# ESC_2S.net
KiCad netlist of a schematic drawn in Altium Designer
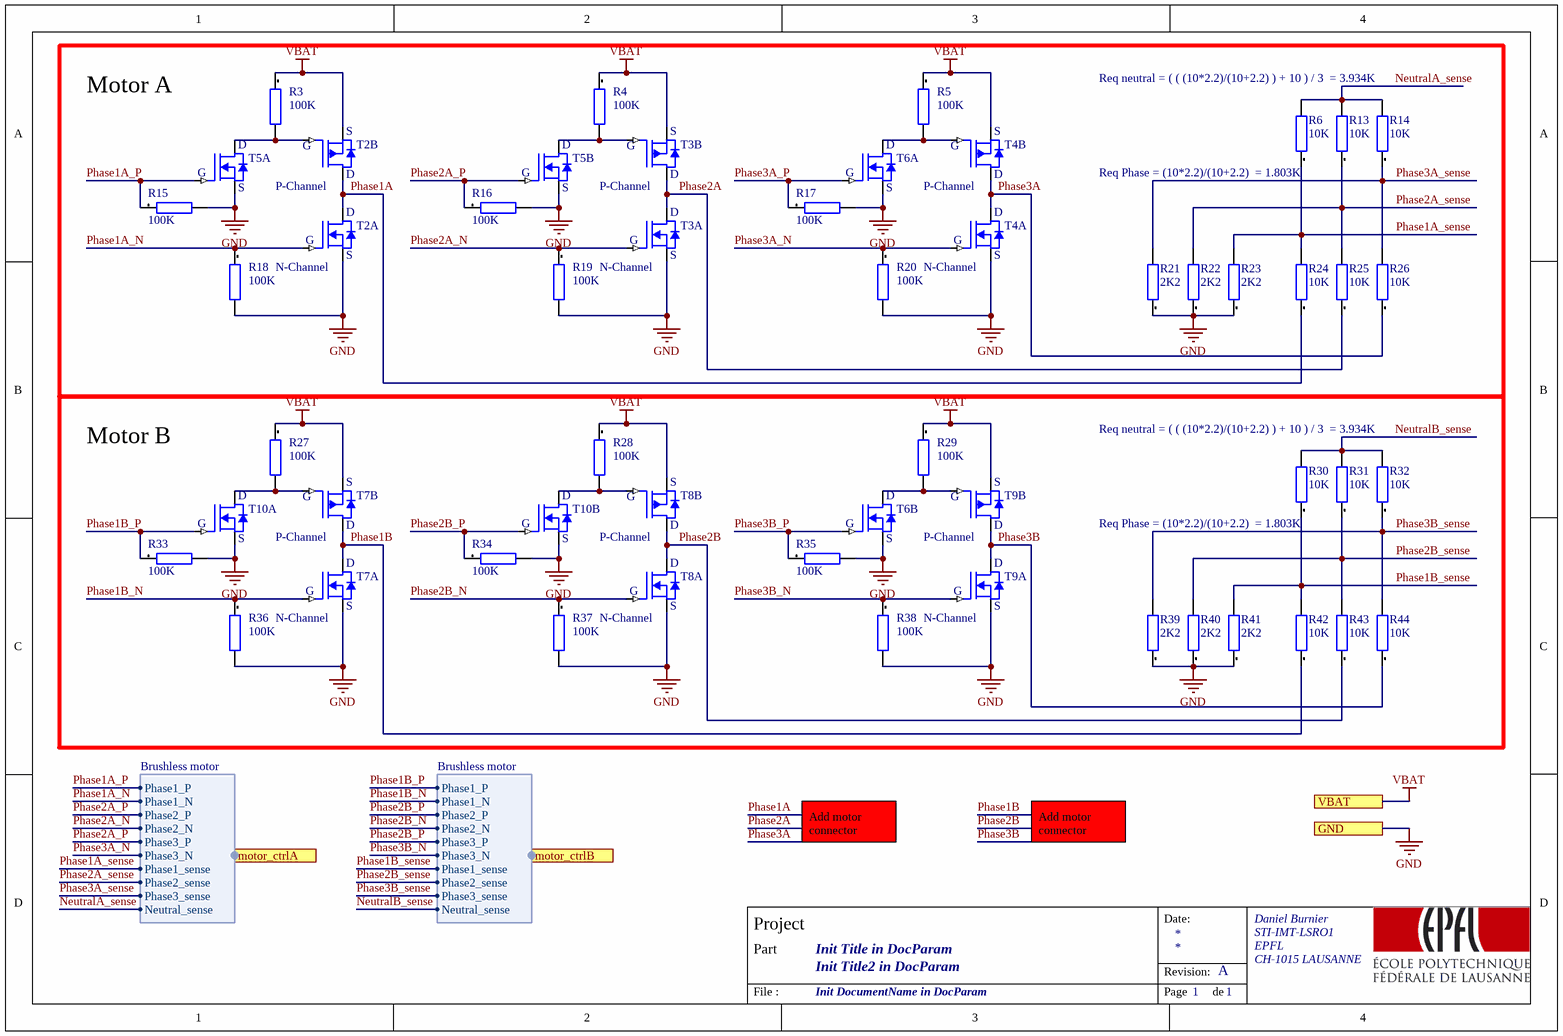
[diagram p0: ESC_2S.SchDoc]

(export (version "E")
  (design (tool "Eeschema 10.0.6"))
  (components
    (comp (ref "R3")
      (value "100K")
      (footprint "RESC0201(0603)_L")
      (description "Resistor ToDo 0201")
      (libsource (lib "LSRO1Altium") (part "RES"))
    )
    (comp (ref "R4")
      (value "100K")
      (footprint "RESC0201(0603)_L")
      (description "Resistor ToDo 0201")
      (libsource (lib "LSRO1Altium") (part "RES"))
    )
    (comp (ref "R5")
      (value "100K")
      (footprint "RESC0201(0603)_L")
      (description "Resistor ToDo 0201")
      (libsource (lib "LSRO1Altium") (part "RES"))
    )
    (comp (ref "R6")
      (value "10K")
      (footprint "RESC0201(0603)_L")
      (description "Resistor ToDo 0201")
      (libsource (lib "LSRO1Altium") (part "RES"))
    )
    (comp (ref "R13")
      (value "10K")
      (footprint "RESC0201(0603)_L")
      (description "Resistor ToDo 0201")
      (libsource (lib "LSRO1Altium") (part "RES"))
    )
    (comp (ref "R14")
      (value "10K")
      (footprint "RESC0201(0603)_L")
      (description "Resistor ToDo 0201")
      (libsource (lib "LSRO1Altium") (part "RES"))
    )
    (comp (ref "R15")
      (value "100K")
      (footprint "RESC0201(0603)_L")
      (description "Resistor ToDo 0201")
      (libsource (lib "LSRO1Altium") (part "RES"))
    )
    (comp (ref "R16")
      (value "100K")
      (footprint "RESC0201(0603)_L")
      (description "Resistor ToDo 0201")
      (libsource (lib "LSRO1Altium") (part "RES"))
    )
    (comp (ref "R17")
      (value "100K")
      (footprint "RESC0201(0603)_L")
      (description "Resistor ToDo 0201")
      (libsource (lib "LSRO1Altium") (part "RES"))
    )
    (comp (ref "R18")
      (value "100K")
      (footprint "RESC0201(0603)_L")
      (description "Resistor ToDo 0201")
      (libsource (lib "LSRO1Altium") (part "RES"))
    )
    (comp (ref "R19")
      (value "100K")
      (footprint "RESC0201(0603)_L")
      (description "Resistor ToDo 0201")
      (libsource (lib "LSRO1Altium") (part "RES"))
    )
    (comp (ref "R20")
      (value "100K")
      (footprint "RESC0201(0603)_L")
      (description "Resistor ToDo 0201")
      (libsource (lib "LSRO1Altium") (part "RES"))
    )
    (comp (ref "R21")
      (value "2K2")
      (footprint "RESC0201(0603)_L")
      (description "Resistor ToDo 0201")
      (libsource (lib "LSRO1Altium") (part "RES"))
    )
    (comp (ref "R22")
      (value "2K2")
      (footprint "RESC0201(0603)_L")
      (description "Resistor ToDo 0201")
      (libsource (lib "LSRO1Altium") (part "RES"))
    )
    (comp (ref "R23")
      (value "2K2")
      (footprint "RESC0201(0603)_L")
      (description "Resistor ToDo 0201")
      (libsource (lib "LSRO1Altium") (part "RES"))
    )
    (comp (ref "R24")
      (value "10K")
      (footprint "RESC0201(0603)_L")
      (description "Resistor ToDo 0201")
      (libsource (lib "LSRO1Altium") (part "RES"))
    )
    (comp (ref "R25")
      (value "10K")
      (footprint "RESC0201(0603)_L")
      (description "Resistor ToDo 0201")
      (libsource (lib "LSRO1Altium") (part "RES"))
    )
    (comp (ref "R26")
      (value "10K")
      (footprint "RESC0201(0603)_L")
      (description "Resistor ToDo 0201")
      (libsource (lib "LSRO1Altium") (part "RES"))
    )
    (comp (ref "R27")
      (value "100K")
      (footprint "RESC0201(0603)_L")
      (description "Resistor ToDo 0201")
      (libsource (lib "LSRO1Altium") (part "RES"))
    )
    (comp (ref "R28")
      (value "100K")
      (footprint "RESC0201(0603)_L")
      (description "Resistor ToDo 0201")
      (libsource (lib "LSRO1Altium") (part "RES"))
    )
    (comp (ref "R29")
      (value "100K")
      (footprint "RESC0201(0603)_L")
      (description "Resistor ToDo 0201")
      (libsource (lib "LSRO1Altium") (part "RES"))
    )
    (comp (ref "R30")
      (value "10K")
      (footprint "RESC0201(0603)_L")
      (description "Resistor ToDo 0201")
      (libsource (lib "LSRO1Altium") (part "RES"))
    )
    (comp (ref "R31")
      (value "10K")
      (footprint "RESC0201(0603)_L")
      (description "Resistor ToDo 0201")
      (libsource (lib "LSRO1Altium") (part "RES"))
    )
    (comp (ref "R32")
      (value "10K")
      (footprint "RESC0201(0603)_L")
      (description "Resistor ToDo 0201")
      (libsource (lib "LSRO1Altium") (part "RES"))
    )
    (comp (ref "R33")
      (value "100K")
      (footprint "RESC0201(0603)_L")
      (description "Resistor ToDo 0201")
      (libsource (lib "LSRO1Altium") (part "RES"))
    )
    (comp (ref "R34")
      (value "100K")
      (footprint "RESC0201(0603)_L")
      (description "Resistor ToDo 0201")
      (libsource (lib "LSRO1Altium") (part "RES"))
    )
    (comp (ref "R35")
      (value "100K")
      (footprint "RESC0201(0603)_L")
      (description "Resistor ToDo 0201")
      (libsource (lib "LSRO1Altium") (part "RES"))
    )
    (comp (ref "R36")
      (value "100K")
      (footprint "RESC0201(0603)_L")
      (description "Resistor ToDo 0201")
      (libsource (lib "LSRO1Altium") (part "RES"))
    )
    (comp (ref "R37")
      (value "100K")
      (footprint "RESC0201(0603)_L")
      (description "Resistor ToDo 0201")
      (libsource (lib "LSRO1Altium") (part "RES"))
    )
    (comp (ref "R38")
      (value "100K")
      (footprint "RESC0201(0603)_L")
      (description "Resistor ToDo 0201")
      (libsource (lib "LSRO1Altium") (part "RES"))
    )
    (comp (ref "R39")
      (value "2K2")
      (footprint "RESC0201(0603)_L")
      (description "Resistor ToDo 0201")
      (libsource (lib "LSRO1Altium") (part "RES"))
    )
    (comp (ref "R40")
      (value "2K2")
      (footprint "RESC0201(0603)_L")
      (description "Resistor ToDo 0201")
      (libsource (lib "LSRO1Altium") (part "RES"))
    )
    (comp (ref "R41")
      (value "2K2")
      (footprint "RESC0201(0603)_L")
      (description "Resistor ToDo 0201")
      (libsource (lib "LSRO1Altium") (part "RES"))
    )
    (comp (ref "R42")
      (value "10K")
      (footprint "RESC0201(0603)_L")
      (description "Resistor ToDo 0201")
      (libsource (lib "LSRO1Altium") (part "RES"))
    )
    (comp (ref "R43")
      (value "10K")
      (footprint "RESC0201(0603)_L")
      (description "Resistor ToDo 0201")
      (libsource (lib "LSRO1Altium") (part "RES"))
    )
    (comp (ref "R44")
      (value "10K")
      (footprint "RESC0201(0603)_L")
      (description "Resistor ToDo 0201")
      (libsource (lib "LSRO1Altium") (part "RES"))
    )
    (comp (ref "T2")
      (value "ECH8668-TL-H")
      (footprint "8-SMD Flat lead")
      (description "MOSFET N/P-CH 20V 7.5A/5A ECH8")
      (fields (field (name "MANUFACTURER") "ON Semiconductor"))
      (libsource (lib "Schlib") (part "ECH8668-TL-H"))
    )
    (comp (ref "T3")
      (value "ECH8668-TL-H")
      (footprint "8-SMD Flat lead")
      (description "MOSFET N/P-CH 20V 7.5A/5A ECH8")
      (fields (field (name "MANUFACTURER") "ON Semiconductor"))
      (libsource (lib "Schlib") (part "ECH8668-TL-H"))
    )
    (comp (ref "T4")
      (value "ECH8668-TL-H")
      (footprint "8-SMD Flat lead")
      (description "MOSFET N/P-CH 20V 7.5A/5A ECH8")
      (fields (field (name "MANUFACTURER") "ON Semiconductor"))
      (libsource (lib "Schlib") (part "ECH8668-TL-H"))
    )
    (comp (ref "T5")
      (value "PMDXB550UNEZ")
      (footprint "DFN1010B-6")
      (description "DUAL N-CHANNEL 30V")
      (fields (field (name "MANUFACTURER") "NXP Semiconductors"))
      (libsource (lib "Schlib") (part "PMDXB550UNEZ"))
    )
    (comp (ref "T6")
      (value "PMDXB550UNEZ")
      (footprint "DFN1010B-6")
      (description "DUAL N-CHANNEL 30V")
      (fields (field (name "MANUFACTURER") "NXP Semiconductors"))
      (libsource (lib "Schlib") (part "PMDXB550UNEZ"))
    )
    (comp (ref "T7")
      (value "ECH8668-TL-H")
      (footprint "8-SMD Flat lead")
      (description "MOSFET N/P-CH 20V 7.5A/5A ECH8")
      (fields (field (name "MANUFACTURER") "ON Semiconductor"))
      (libsource (lib "Schlib") (part "ECH8668-TL-H"))
    )
    (comp (ref "T8")
      (value "ECH8668-TL-H")
      (footprint "8-SMD Flat lead")
      (description "MOSFET N/P-CH 20V 7.5A/5A ECH8")
      (fields (field (name "MANUFACTURER") "ON Semiconductor"))
      (libsource (lib "Schlib") (part "ECH8668-TL-H"))
    )
    (comp (ref "T9")
      (value "ECH8668-TL-H")
      (footprint "8-SMD Flat lead")
      (description "MOSFET N/P-CH 20V 7.5A/5A ECH8")
      (fields (field (name "MANUFACTURER") "ON Semiconductor"))
      (libsource (lib "Schlib") (part "ECH8668-TL-H"))
    )
    (comp (ref "T10")
      (value "PMDXB550UNEZ")
      (footprint "DFN1010B-6")
      (description "DUAL N-CHANNEL 30V")
      (fields (field (name "MANUFACTURER") "NXP Semiconductors"))
      (libsource (lib "Schlib") (part "PMDXB550UNEZ"))
    )
  )
  (nets
    (net (code "3") (name "/NeutralA_sense") (class "Default")
      (node (ref "R13") (pin "2") (pinfunction "2_2") (pintype "passive"))
      (node (ref "R14") (pin "2") (pinfunction "2_2") (pintype "passive"))
      (node (ref "R6") (pin "2") (pinfunction "2_2") (pintype "passive"))
    )
    (net (code "4") (name "/NeutralB_sense") (class "Default")
      (node (ref "R30") (pin "2") (pinfunction "2_2") (pintype "passive"))
      (node (ref "R31") (pin "2") (pinfunction "2_2") (pintype "passive"))
      (node (ref "R32") (pin "2") (pinfunction "2_2") (pintype "passive"))
    )
    (net (code "5") (name "/Phase1A") (class "Default")
      (node (ref "R24") (pin "1") (pinfunction "1_1") (pintype "passive"))
      (node (ref "T2") (pin "5") (pinfunction "D_5") (pintype "passive"))
      (node (ref "T2") (pin "6") (pinfunction "D_6") (pintype "passive"))
    )
    (net (code "6") (name "/Phase1A_N") (class "Default")
      (node (ref "R18") (pin "1") (pinfunction "1_1") (pintype "passive"))
      (node (ref "T2") (pin "2") (pinfunction "G_2") (pintype "input"))
    )
    (net (code "7") (name "/Phase1A_P") (class "Default")
      (node (ref "R15") (pin "1") (pinfunction "1_1") (pintype "passive"))
      (node (ref "T5") (pin "2") (pinfunction "G_2") (pintype "input"))
    )
    (net (code "8") (name "/Phase1A_sense") (class "Default")
      (node (ref "R23") (pin "2") (pinfunction "2_2") (pintype "passive"))
      (node (ref "R24") (pin "2") (pinfunction "2_2") (pintype "passive"))
      (node (ref "R6") (pin "1") (pinfunction "1_1") (pintype "passive"))
    )
    (net (code "9") (name "/Phase1B") (class "Default")
      (node (ref "R42") (pin "1") (pinfunction "1_1") (pintype "passive"))
      (node (ref "T7") (pin "5") (pinfunction "D_5") (pintype "passive"))
      (node (ref "T7") (pin "6") (pinfunction "D_6") (pintype "passive"))
    )
    (net (code "10") (name "/Phase1B_N") (class "Default")
      (node (ref "R36") (pin "1") (pinfunction "1_1") (pintype "passive"))
      (node (ref "T7") (pin "2") (pinfunction "G_2") (pintype "input"))
    )
    (net (code "11") (name "/Phase1B_P") (class "Default")
      (node (ref "R33") (pin "1") (pinfunction "1_1") (pintype "passive"))
      (node (ref "T10") (pin "2") (pinfunction "G_2") (pintype "input"))
    )
    (net (code "12") (name "/Phase1B_sense") (class "Default")
      (node (ref "R30") (pin "1") (pinfunction "1_1") (pintype "passive"))
      (node (ref "R41") (pin "2") (pinfunction "2_2") (pintype "passive"))
      (node (ref "R42") (pin "2") (pinfunction "2_2") (pintype "passive"))
    )
    (net (code "13") (name "/Phase2A") (class "Default")
      (node (ref "R25") (pin "1") (pinfunction "1_1") (pintype "passive"))
      (node (ref "T3") (pin "5") (pinfunction "D_5") (pintype "passive"))
      (node (ref "T3") (pin "6") (pinfunction "D_6") (pintype "passive"))
    )
    (net (code "14") (name "/Phase2A_N") (class "Default")
      (node (ref "R19") (pin "1") (pinfunction "1_1") (pintype "passive"))
      (node (ref "T3") (pin "2") (pinfunction "G_2") (pintype "input"))
    )
    (net (code "15") (name "/Phase2A_P") (class "Default")
      (node (ref "R16") (pin "1") (pinfunction "1_1") (pintype "passive"))
      (node (ref "T5") (pin "5") (pinfunction "G_5") (pintype "input"))
    )
    (net (code "16") (name "/Phase2A_sense") (class "Default")
      (node (ref "R13") (pin "1") (pinfunction "1_1") (pintype "passive"))
      (node (ref "R22") (pin "2") (pinfunction "2_2") (pintype "passive"))
      (node (ref "R25") (pin "2") (pinfunction "2_2") (pintype "passive"))
    )
    (net (code "17") (name "/Phase2B") (class "Default")
      (node (ref "R43") (pin "1") (pinfunction "1_1") (pintype "passive"))
      (node (ref "T8") (pin "5") (pinfunction "D_5") (pintype "passive"))
      (node (ref "T8") (pin "6") (pinfunction "D_6") (pintype "passive"))
    )
    (net (code "18") (name "/Phase2B_N") (class "Default")
      (node (ref "R37") (pin "1") (pinfunction "1_1") (pintype "passive"))
      (node (ref "T8") (pin "2") (pinfunction "G_2") (pintype "input"))
    )
    (net (code "19") (name "/Phase2B_P") (class "Default")
      (node (ref "R34") (pin "1") (pinfunction "1_1") (pintype "passive"))
      (node (ref "T10") (pin "5") (pinfunction "G_5") (pintype "input"))
    )
    (net (code "20") (name "/Phase2B_sense") (class "Default")
      (node (ref "R31") (pin "1") (pinfunction "1_1") (pintype "passive"))
      (node (ref "R40") (pin "2") (pinfunction "2_2") (pintype "passive"))
      (node (ref "R43") (pin "2") (pinfunction "2_2") (pintype "passive"))
    )
    (net (code "21") (name "/Phase3A") (class "Default")
      (node (ref "R26") (pin "1") (pinfunction "1_1") (pintype "passive"))
      (node (ref "T4") (pin "5") (pinfunction "D_5") (pintype "passive"))
      (node (ref "T4") (pin "6") (pinfunction "D_6") (pintype "passive"))
    )
    (net (code "22") (name "/Phase3A_N") (class "Default")
      (node (ref "R20") (pin "1") (pinfunction "1_1") (pintype "passive"))
      (node (ref "T4") (pin "2") (pinfunction "G_2") (pintype "input"))
    )
    (net (code "23") (name "/Phase3A_P") (class "Default")
      (node (ref "R17") (pin "1") (pinfunction "1_1") (pintype "passive"))
      (node (ref "T6") (pin "2") (pinfunction "G_2") (pintype "input"))
    )
    (net (code "24") (name "/Phase3A_sense") (class "Default")
      (node (ref "R14") (pin "1") (pinfunction "1_1") (pintype "passive"))
      (node (ref "R21") (pin "2") (pinfunction "2_2") (pintype "passive"))
      (node (ref "R26") (pin "2") (pinfunction "2_2") (pintype "passive"))
    )
    (net (code "25") (name "/Phase3B") (class "Default")
      (node (ref "R44") (pin "1") (pinfunction "1_1") (pintype "passive"))
      (node (ref "T9") (pin "5") (pinfunction "D_5") (pintype "passive"))
      (node (ref "T9") (pin "6") (pinfunction "D_6") (pintype "passive"))
    )
    (net (code "26") (name "/Phase3B_N") (class "Default")
      (node (ref "R38") (pin "1") (pinfunction "1_1") (pintype "passive"))
      (node (ref "T9") (pin "2") (pinfunction "G_2") (pintype "input"))
    )
    (net (code "27") (name "/Phase3B_P") (class "Default")
      (node (ref "R35") (pin "1") (pinfunction "1_1") (pintype "passive"))
      (node (ref "T6") (pin "5") (pinfunction "G_5") (pintype "input"))
    )
    (net (code "28") (name "/Phase3B_sense") (class "Default")
      (node (ref "R32") (pin "1") (pinfunction "1_1") (pintype "passive"))
      (node (ref "R39") (pin "2") (pinfunction "2_2") (pintype "passive"))
      (node (ref "R44") (pin "2") (pinfunction "2_2") (pintype "passive"))
    )
    (net (code "30") (name "GND") (class "Default")
      (node (ref "R15") (pin "2") (pinfunction "2_2") (pintype "passive"))
      (node (ref "R16") (pin "2") (pinfunction "2_2") (pintype "passive"))
      (node (ref "R17") (pin "2") (pinfunction "2_2") (pintype "passive"))
      (node (ref "R18") (pin "2") (pinfunction "2_2") (pintype "passive"))
      (node (ref "R19") (pin "2") (pinfunction "2_2") (pintype "passive"))
      (node (ref "R20") (pin "2") (pinfunction "2_2") (pintype "passive"))
      (node (ref "R21") (pin "1") (pinfunction "1_1") (pintype "passive"))
      (node (ref "R22") (pin "1") (pinfunction "1_1") (pintype "passive"))
      (node (ref "R23") (pin "1") (pinfunction "1_1") (pintype "passive"))
      (node (ref "R33") (pin "2") (pinfunction "2_2") (pintype "passive"))
      (node (ref "R34") (pin "2") (pinfunction "2_2") (pintype "passive"))
      (node (ref "R35") (pin "2") (pinfunction "2_2") (pintype "passive"))
      (node (ref "R36") (pin "2") (pinfunction "2_2") (pintype "passive"))
      (node (ref "R37") (pin "2") (pinfunction "2_2") (pintype "passive"))
      (node (ref "R38") (pin "2") (pinfunction "2_2") (pintype "passive"))
      (node (ref "R39") (pin "1") (pinfunction "1_1") (pintype "passive"))
      (node (ref "R40") (pin "1") (pinfunction "1_1") (pintype "passive"))
      (node (ref "R41") (pin "1") (pinfunction "1_1") (pintype "passive"))
      (node (ref "T10") (pin "1") (pinfunction "S_1") (pintype "passive"))
      (node (ref "T10") (pin "4") (pinfunction "S_4") (pintype "passive"))
      (node (ref "T2") (pin "1") (pinfunction "S_1") (pintype "passive"))
      (node (ref "T3") (pin "1") (pinfunction "S_1") (pintype "passive"))
      (node (ref "T4") (pin "1") (pinfunction "S_1") (pintype "passive"))
      (node (ref "T5") (pin "1") (pinfunction "S_1") (pintype "passive"))
      (node (ref "T5") (pin "4") (pinfunction "S_4") (pintype "passive"))
      (node (ref "T6") (pin "1") (pinfunction "S_1") (pintype "passive"))
      (node (ref "T6") (pin "4") (pinfunction "S_4") (pintype "passive"))
      (node (ref "T7") (pin "1") (pinfunction "S_1") (pintype "passive"))
      (node (ref "T8") (pin "1") (pinfunction "S_1") (pintype "passive"))
      (node (ref "T9") (pin "1") (pinfunction "S_1") (pintype "passive"))
    )
    (net (code "31") (name "Net-(T2B-G)") (class "Default")
      (node (ref "R3") (pin "2") (pinfunction "2_2") (pintype "passive"))
      (node (ref "T2") (pin "4") (pinfunction "G_4") (pintype "input"))
      (node (ref "T5") (pin "6") (pinfunction "D_6") (pintype "passive"))
    )
    (net (code "32") (name "Net-(T3B-G)") (class "Default")
      (node (ref "R4") (pin "2") (pinfunction "2_2") (pintype "passive"))
      (node (ref "T3") (pin "4") (pinfunction "G_4") (pintype "input"))
      (node (ref "T5") (pin "3") (pinfunction "D_3") (pintype "passive"))
    )
    (net (code "33") (name "Net-(T4B-G)") (class "Default")
      (node (ref "R5") (pin "2") (pinfunction "2_2") (pintype "passive"))
      (node (ref "T4") (pin "4") (pinfunction "G_4") (pintype "input"))
      (node (ref "T6") (pin "6") (pinfunction "D_6") (pintype "passive"))
    )
    (net (code "34") (name "Net-(T6B-D)") (class "Default")
      (node (ref "R29") (pin "2") (pinfunction "2_2") (pintype "passive"))
      (node (ref "T6") (pin "3") (pinfunction "D_3") (pintype "passive"))
      (node (ref "T9") (pin "4") (pinfunction "G_4") (pintype "input"))
    )
    (net (code "35") (name "Net-(T10A-D)") (class "Default")
      (node (ref "R27") (pin "2") (pinfunction "2_2") (pintype "passive"))
      (node (ref "T10") (pin "6") (pinfunction "D_6") (pintype "passive"))
      (node (ref "T7") (pin "4") (pinfunction "G_4") (pintype "input"))
    )
    (net (code "36") (name "Net-(T10B-D)") (class "Default")
      (node (ref "R28") (pin "2") (pinfunction "2_2") (pintype "passive"))
      (node (ref "T10") (pin "3") (pinfunction "D_3") (pintype "passive"))
      (node (ref "T8") (pin "4") (pinfunction "G_4") (pintype "input"))
    )
    (net (code "37") (name "VBAT") (class "Default")
      (node (ref "R27") (pin "1") (pinfunction "1_1") (pintype "passive"))
      (node (ref "R28") (pin "1") (pinfunction "1_1") (pintype "passive"))
      (node (ref "R29") (pin "1") (pinfunction "1_1") (pintype "passive"))
      (node (ref "R3") (pin "1") (pinfunction "1_1") (pintype "passive"))
      (node (ref "R4") (pin "1") (pinfunction "1_1") (pintype "passive"))
      (node (ref "R5") (pin "1") (pinfunction "1_1") (pintype "passive"))
      (node (ref "T2") (pin "3") (pinfunction "S_3") (pintype "passive"))
      (node (ref "T3") (pin "3") (pinfunction "S_3") (pintype "passive"))
      (node (ref "T4") (pin "3") (pinfunction "S_3") (pintype "passive"))
      (node (ref "T7") (pin "3") (pinfunction "S_3") (pintype "passive"))
      (node (ref "T8") (pin "3") (pinfunction "S_3") (pintype "passive"))
      (node (ref "T9") (pin "3") (pinfunction "S_3") (pintype "passive"))
    )
  )
)
